# Protection_Stage.net
KiCad netlist of a schematic drawn in Altium Designer
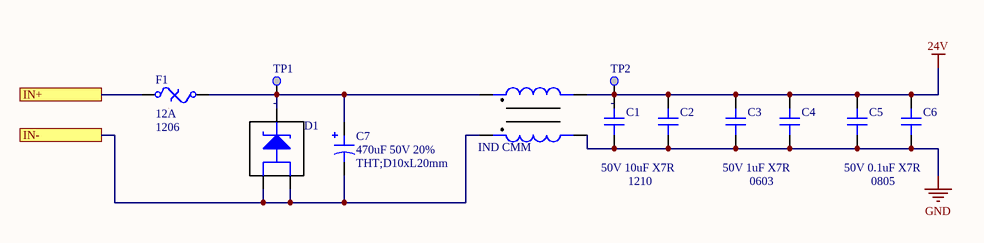
[diagram p0: Protection_Stage.SchDoc]

(export (version "E")
  (design (tool "Eeschema 10.0.6"))
  (components
    (comp (ref "C1")
      (value "50V 10uF X7R")
      (footprint "CAP SMD 1210")
      (description "Condensadores de cerámica multicapa (MLCC- SMD/SMT) WCAP-CSGP 10uF 50Vol 0.1")
      (fields
        (field (name "PACKAGE") "1210")
        (field (name "MPN") "885012209073")
        (field (name "MANUFACTURER") "Wurth Elektronik")
      )
      (libsource (lib "eUSR_Database") (part "CAP non polarized"))
    )
    (comp (ref "C2")
      (value "CAP non polarized")
      (footprint "CAP SMD 1210")
      (description "Condensadores de cerámica multicapa (MLCC- SMD/SMT) WCAP-CSGP 10uF 50Vol 0.1")
      (fields (field (name "MPN") "885012209073") (field (name "MANUFACTURER") "Wurth Elektronik"))
      (libsource (lib "eUSR_Database") (part "CAP non polarized"))
    )
    (comp (ref "C3")
      (value "50V 1uF X7R")
      (footprint "CAP SMD 0603")
      (description "Condensadores de cerámica multicapa (MLCC- SMD/SMT) WCAP-CSGP 1uF 50 Vol 10%")
      (fields
        (field (name "PACKAGE") "0603")
        (field (name "MPN") "885012206126")
        (field (name "MANUFACTURER") "Wurth Elektronik")
      )
      (libsource (lib "eUSR_Database") (part "CAP non polarized"))
    )
    (comp (ref "C4")
      (value "CAP non polarized")
      (footprint "CAP SMD 0603")
      (description "Condensadores de cerámica multicapa (MLCC- SMD/SMT) WCAP-CSGP 1uF 50 Vol 10%")
      (fields (field (name "MPN") "885012206126") (field (name "MANUFACTURER") "Wurth Elektronik"))
      (libsource (lib "eUSR_Database") (part "CAP non polarized"))
    )
    (comp (ref "C5")
      (value "50V 0.1uF X7R")
      (footprint "CAP SMD 0805")
      (description "Condensadores de cerámica multicapa (MLCC- SMD/SMT) WCAP-CSGP 0.1uF 0805 10% 50V MLCC")
      (fields
        (field (name "PACKAGE") "0805")
        (field (name "MPN") "885012207098")
        (field (name "MANUFACTURER") "Wurth Elektronik")
      )
      (libsource (lib "eUSR_Database") (part "CAP non polarized"))
    )
    (comp (ref "C6")
      (value "CAP non polarized")
      (footprint "CAP SMD 0805")
      (description "Condensadores de cerámica multicapa (MLCC- SMD/SMT) WCAP-CSGP 0.1uF 0805 10% 50V MLCC")
      (fields (field (name "MPN") "885012207098") (field (name "MANUFACTURER") "Wurth Elektronik"))
      (libsource (lib "eUSR_Database") (part "CAP non polarized"))
    )
    (comp (ref "C7")
      (value "470uF 50V 20%")
      (footprint "CAP_10Dx20L")
      (description "Aluminium Electrolytic Capacitors - Radial Leaded WCAP-ATG5 470uF 50V 20% Radial")
      (fields
        (field (name "PACKAGE") "THT;D10xL20mm")
        (field (name "MPN") "860020675022")
        (field (name "MANUFACTURER") "Wurth Elektonik")
      )
      (libsource (lib "eUSR_Database") (part "CAP polarized"))
    )
    (comp (ref "D1")
      (value "DIODE SCHOTTKY 3P")
      (footprint "TO-277A-3")
      (description "Diodos y rectificadores Schottky 20A,100VG2PSKYSMPCRect.")
      (fields (field (name "MPN") "SS20PH102HM3/I") (field (name "MANUFACTURER") "Vishay Semiconductors"))
      (libsource (lib "eUSR_Database") (part "DIODE SCHOTTKY 3P"))
    )
    (comp (ref "F1")
      (value "12A")
      (footprint "FUSE SMD 1206")
      (description "Surface Mount Fuses 12A 32V FAST ACTING")
      (fields
        (field (name "PACKAGE") "1206")
        (field (name "MPN") "0501012.WRA")
        (field (name "MANUFACTURER") "Littelfuse")
      )
      (libsource (lib "eUSR_Database") (part "FUSE"))
    )
    (comp (ref "L1")
      (value "IND CMM")
      (footprint "IND_CMM_THT_10x18.5mm")
      (description "Common Mode Chokes / Filters WE-CMB Type XXL .5mH 35A 2.3mOhm")
      (fields (field (name "MPN") "7448263505") (field (name "MANUFACTURER") "Wurth Elektronik"))
      (libsource (lib "eUSR_Database") (part "IND CMM"))
    )
    (comp (ref "TP1")
      (value "-")
      (footprint "TP_SMD_1MM")
      (description "Test Point")
      (libsource (lib "eUSR_Database") (part "TP1mm"))
    )
    (comp (ref "TP2")
      (value "-")
      (footprint "TP_SMD_1MM")
      (description "Test Point")
      (libsource (lib "eUSR_Database") (part "TP1mm"))
    )
  )
  (nets
    (net (code "1") (name "/IN+") (class "Default")
      (node (ref "F1") (pin "1") (pinfunction "1_1") (pintype "passive"))
    )
    (net (code "2") (name "/IN-") (class "Default")
      (node (ref "C7") (pin "N") (pinfunction "N_N") (pintype "passive"))
      (node (ref "D1") (pin "1") (pinfunction "1_1") (pintype "passive"))
      (node (ref "D1") (pin "2") (pinfunction "2_2") (pintype "passive"))
      (node (ref "L1") (pin "4") (pinfunction "4_4") (pintype "passive"))
    )
    (net (code "3") (name "24V") (class "Default")
      (node (ref "C1") (pin "1") (pinfunction "1_1") (pintype "passive"))
      (node (ref "C2") (pin "1") (pinfunction "1_1") (pintype "passive"))
      (node (ref "C3") (pin "1") (pinfunction "1_1") (pintype "passive"))
      (node (ref "C4") (pin "1") (pinfunction "1_1") (pintype "passive"))
      (node (ref "C5") (pin "1") (pinfunction "1_1") (pintype "passive"))
      (node (ref "C6") (pin "1") (pinfunction "1_1") (pintype "passive"))
      (node (ref "L1") (pin "2") (pinfunction "2_2") (pintype "passive"))
      (node (ref "TP2") (pin "1") (pinfunction "1_1") (pintype "passive"))
    )
    (net (code "4") (name "GND") (class "Default")
      (node (ref "C1") (pin "2") (pinfunction "2_2") (pintype "passive"))
      (node (ref "C2") (pin "2") (pinfunction "2_2") (pintype "passive"))
      (node (ref "C3") (pin "2") (pinfunction "2_2") (pintype "passive"))
      (node (ref "C4") (pin "2") (pinfunction "2_2") (pintype "passive"))
      (node (ref "C5") (pin "2") (pinfunction "2_2") (pintype "passive"))
      (node (ref "C6") (pin "2") (pinfunction "2_2") (pintype "passive"))
      (node (ref "L1") (pin "3") (pinfunction "3_3") (pintype "passive"))
    )
    (net (code "5") (name "Net-(C7-PadP)") (class "Default")
      (node (ref "C7") (pin "P") (pinfunction "P_P") (pintype "passive"))
      (node (ref "D1") (pin "3") (pinfunction "3_3") (pintype "passive"))
      (node (ref "F1") (pin "2") (pinfunction "2_2") (pintype "passive"))
      (node (ref "L1") (pin "1") (pinfunction "1_1") (pintype "passive"))
      (node (ref "TP1") (pin "1") (pinfunction "1_1") (pintype "passive"))
    )
  )
)
